# main.net
KiCad netlist of a schematic drawn in EAGLE
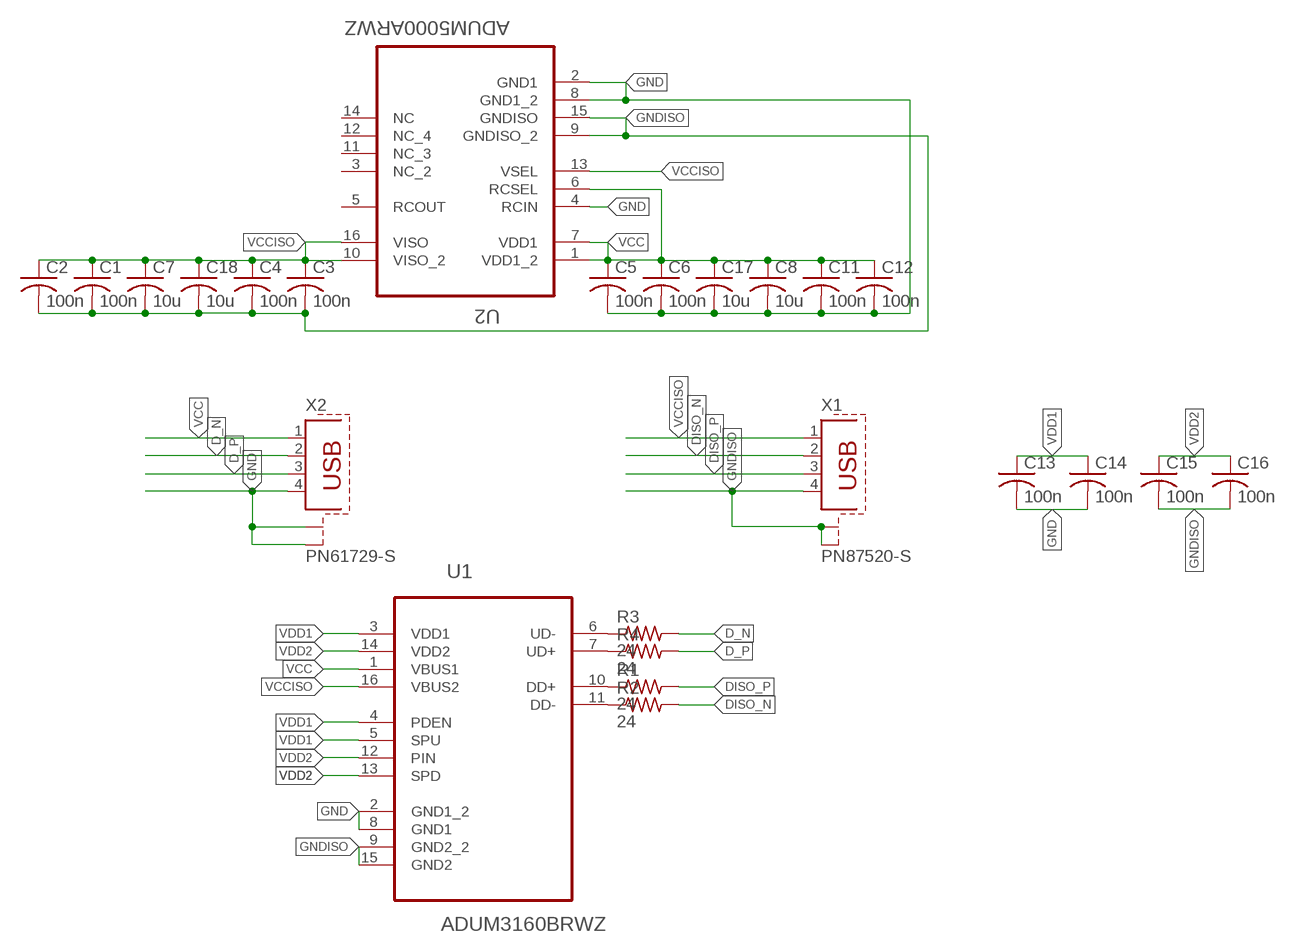
[diagram p0: schematic, sheet 1]

(export (version "E")
  (design (tool "Eeschema 10.0.6"))
  (components
    (comp (ref "C1")
      (value "100n")
      (footprint "eagle-import:C0603")
      (libsource (lib "eagle-import") (part "C-USC0603"))
    )
    (comp (ref "C2")
      (value "100n")
      (footprint "eagle-import:C0603")
      (libsource (lib "eagle-import") (part "C-USC0603"))
    )
    (comp (ref "C3")
      (value "100n")
      (footprint "eagle-import:C0603")
      (libsource (lib "eagle-import") (part "C-USC0603"))
    )
    (comp (ref "C4")
      (value "100n")
      (footprint "eagle-import:C0603")
      (libsource (lib "eagle-import") (part "C-USC0603"))
    )
    (comp (ref "C5")
      (value "100n")
      (footprint "eagle-import:C0603")
      (libsource (lib "eagle-import") (part "C-USC0603"))
    )
    (comp (ref "C6")
      (value "100n")
      (footprint "eagle-import:C0603")
      (libsource (lib "eagle-import") (part "C-USC0603"))
    )
    (comp (ref "C7")
      (value "10u")
      (footprint "eagle-import:C025-025X050")
      (libsource (lib "eagle-import") (part "C-US025-025X050"))
    )
    (comp (ref "C8")
      (value "10u")
      (footprint "eagle-import:C025-025X050")
      (libsource (lib "eagle-import") (part "C-US025-025X050"))
    )
    (comp (ref "C11")
      (value "100n")
      (footprint "eagle-import:C0603")
      (libsource (lib "eagle-import") (part "C-USC0603"))
    )
    (comp (ref "C12")
      (value "100n")
      (footprint "eagle-import:C0603")
      (libsource (lib "eagle-import") (part "C-USC0603"))
    )
    (comp (ref "C13")
      (value "100n")
      (footprint "eagle-import:C0603")
      (libsource (lib "eagle-import") (part "C-USC0603"))
    )
    (comp (ref "C14")
      (value "100n")
      (footprint "eagle-import:C0603")
      (libsource (lib "eagle-import") (part "C-USC0603"))
    )
    (comp (ref "C15")
      (value "100n")
      (footprint "eagle-import:C0603")
      (libsource (lib "eagle-import") (part "C-USC0603"))
    )
    (comp (ref "C16")
      (value "100n")
      (footprint "eagle-import:C0603")
      (libsource (lib "eagle-import") (part "C-USC0603"))
    )
    (comp (ref "C17")
      (value "10u")
      (footprint "eagle-import:C025-025X050")
      (libsource (lib "eagle-import") (part "C-US025-025X050"))
    )
    (comp (ref "C18")
      (value "10u")
      (footprint "eagle-import:C025-025X050")
      (libsource (lib "eagle-import") (part "C-US025-025X050"))
    )
    (comp (ref "R1")
      (value "24")
      (footprint "eagle-import:R0603")
      (libsource (lib "eagle-import") (part "R-US_R0603"))
    )
    (comp (ref "R2")
      (value "24")
      (footprint "eagle-import:R0603")
      (libsource (lib "eagle-import") (part "R-US_R0603"))
    )
    (comp (ref "R3")
      (value "24")
      (footprint "eagle-import:R0603")
      (libsource (lib "eagle-import") (part "R-US_R0603"))
    )
    (comp (ref "R4")
      (value "24")
      (footprint "eagle-import:R0603")
      (libsource (lib "eagle-import") (part "R-US_R0603"))
    )
    (comp (ref "U1")
      (value "ADUM3160BRWZ")
      (footprint "eagle-import:SOIC127P1032X265-16N")
      (libsource (lib "eagle-import") (part "ADUM3160BRWZ"))
    )
    (comp (ref "U2")
      (value "ADUM5000ARWZ")
      (footprint "eagle-import:SOIC127P1032X265-16N")
      (libsource (lib "eagle-import") (part "ADUM5000ARWZ"))
    )
    (comp (ref "X1")
      (value "PN87520-S")
      (footprint "eagle-import:PN87520-S")
      (libsource (lib "eagle-import") (part "PN87520-S"))
    )
    (comp (ref "X2")
      (value "PN61729-S")
      (footprint "eagle-import:PN61729-S")
      (libsource (lib "eagle-import") (part "PN61729-S"))
    )
  )
  (nets
    (net (code "1") (name "DISO_N") (class "Default")
      (node (ref "R2") (pin "2") (pinfunction "2_2") (pintype "passive"))
      (node (ref "X1") (pin "2") (pinfunction "2_2") (pintype "passive"))
    )
    (net (code "2") (name "DISO_P") (class "Default")
      (node (ref "R1") (pin "2") (pinfunction "2_2") (pintype "passive"))
      (node (ref "X1") (pin "3") (pinfunction "3_3") (pintype "passive"))
    )
    (net (code "3") (name "D_N") (class "Default")
      (node (ref "R3") (pin "2") (pinfunction "2_2") (pintype "passive"))
      (node (ref "X2") (pin "2") (pinfunction "2_2") (pintype "passive"))
    )
    (net (code "4") (name "D_P") (class "Default")
      (node (ref "R4") (pin "2") (pinfunction "2_2") (pintype "passive"))
      (node (ref "X2") (pin "3") (pinfunction "3_3") (pintype "passive"))
    )
    (net (code "5") (name "GND") (class "Default")
      (node (ref "C11") (pin "2") (pinfunction "2_2") (pintype "passive"))
      (node (ref "C12") (pin "2") (pinfunction "2_2") (pintype "passive"))
      (node (ref "C13") (pin "2") (pinfunction "2_2") (pintype "passive"))
      (node (ref "C14") (pin "2") (pinfunction "2_2") (pintype "passive"))
      (node (ref "C17") (pin "2") (pinfunction "2_2") (pintype "passive"))
      (node (ref "C5") (pin "2") (pinfunction "2_2") (pintype "passive"))
      (node (ref "C6") (pin "2") (pinfunction "2_2") (pintype "passive"))
      (node (ref "C8") (pin "2") (pinfunction "2_2") (pintype "passive"))
      (node (ref "U1") (pin "2") (pinfunction "GND1_2_2") (pintype "passive"))
      (node (ref "U1") (pin "8") (pinfunction "GND1_8") (pintype "passive"))
      (node (ref "U2") (pin "2") (pinfunction "GND1_2") (pintype "passive"))
      (node (ref "U2") (pin "4") (pinfunction "RCIN_4") (pintype "input"))
      (node (ref "U2") (pin "8") (pinfunction "GND1_2_8") (pintype "passive"))
      (node (ref "X2") (pin "4") (pinfunction "4_4") (pintype "passive"))
      (node (ref "X2") (pin "S1") (pinfunction "S1_S1") (pintype "passive"))
      (node (ref "X2") (pin "S2") (pinfunction "S2_S2") (pintype "passive"))
    )
    (net (code "6") (name "GNDISO") (class "Default")
      (node (ref "C1") (pin "2") (pinfunction "2_2") (pintype "passive"))
      (node (ref "C15") (pin "2") (pinfunction "2_2") (pintype "passive"))
      (node (ref "C16") (pin "2") (pinfunction "2_2") (pintype "passive"))
      (node (ref "C18") (pin "2") (pinfunction "2_2") (pintype "passive"))
      (node (ref "C2") (pin "2") (pinfunction "2_2") (pintype "passive"))
      (node (ref "C3") (pin "2") (pinfunction "2_2") (pintype "passive"))
      (node (ref "C4") (pin "2") (pinfunction "2_2") (pintype "passive"))
      (node (ref "C7") (pin "2") (pinfunction "2_2") (pintype "passive"))
      (node (ref "U1") (pin "15") (pinfunction "GND2_15") (pintype "passive"))
      (node (ref "U1") (pin "9") (pinfunction "GND2_2_9") (pintype "passive"))
      (node (ref "U2") (pin "15") (pinfunction "GNDISO_15") (pintype "passive"))
      (node (ref "U2") (pin "9") (pinfunction "GNDISO_2_9") (pintype "passive"))
      (node (ref "X1") (pin "4") (pinfunction "4_4") (pintype "passive"))
      (node (ref "X1") (pin "S1") (pinfunction "S1_S1") (pintype "passive"))
      (node (ref "X1") (pin "S2") (pinfunction "S2_S2") (pintype "passive"))
    )
    (net (code "7") (name "Net-(U1-DD+)") (class "Default")
      (node (ref "R1") (pin "1") (pinfunction "1_1") (pintype "passive"))
      (node (ref "U1") (pin "10") (pinfunction "DD+_10") (pintype "bidirectional"))
    )
    (net (code "8") (name "Net-(U1-DD-)") (class "Default")
      (node (ref "R2") (pin "1") (pinfunction "1_1") (pintype "passive"))
      (node (ref "U1") (pin "11") (pinfunction "DD-_11") (pintype "bidirectional"))
    )
    (net (code "9") (name "Net-(U1-UD+)") (class "Default")
      (node (ref "R4") (pin "1") (pinfunction "1_1") (pintype "passive"))
      (node (ref "U1") (pin "7") (pinfunction "UD+_7") (pintype "bidirectional"))
    )
    (net (code "10") (name "Net-(U1-UD-)") (class "Default")
      (node (ref "R3") (pin "1") (pinfunction "1_1") (pintype "passive"))
      (node (ref "U1") (pin "6") (pinfunction "UD-_6") (pintype "bidirectional"))
    )
    (net (code "11") (name "VCC") (class "Default")
      (node (ref "C11") (pin "1") (pinfunction "1_1") (pintype "passive"))
      (node (ref "C12") (pin "1") (pinfunction "1_1") (pintype "passive"))
      (node (ref "C17") (pin "1") (pinfunction "1_1") (pintype "passive"))
      (node (ref "C5") (pin "1") (pinfunction "1_1") (pintype "passive"))
      (node (ref "C6") (pin "1") (pinfunction "1_1") (pintype "passive"))
      (node (ref "C8") (pin "1") (pinfunction "1_1") (pintype "passive"))
      (node (ref "U1") (pin "1") (pinfunction "VBUS1_1") (pintype "power_in"))
      (node (ref "U2") (pin "1") (pinfunction "VDD1_2_1") (pintype "power_in"))
      (node (ref "U2") (pin "6") (pinfunction "RCSEL_6") (pintype "input"))
      (node (ref "U2") (pin "7") (pinfunction "VDD1_7") (pintype "power_in"))
      (node (ref "X2") (pin "1") (pinfunction "1_1") (pintype "passive"))
    )
    (net (code "12") (name "VCCISO") (class "Default")
      (node (ref "C1") (pin "1") (pinfunction "1_1") (pintype "passive"))
      (node (ref "C18") (pin "1") (pinfunction "1_1") (pintype "passive"))
      (node (ref "C2") (pin "1") (pinfunction "1_1") (pintype "passive"))
      (node (ref "C3") (pin "1") (pinfunction "1_1") (pintype "passive"))
      (node (ref "C4") (pin "1") (pinfunction "1_1") (pintype "passive"))
      (node (ref "C7") (pin "1") (pinfunction "1_1") (pintype "passive"))
      (node (ref "U1") (pin "16") (pinfunction "VBUS2_16") (pintype "power_in"))
      (node (ref "U2") (pin "10") (pinfunction "VISO_2_10") (pintype "output"))
      (node (ref "U2") (pin "13") (pinfunction "VSEL_13") (pintype "input"))
      (node (ref "U2") (pin "16") (pinfunction "VISO_16") (pintype "output"))
      (node (ref "X1") (pin "1") (pinfunction "1_1") (pintype "passive"))
    )
    (net (code "13") (name "VDD1") (class "Default")
      (node (ref "C13") (pin "1") (pinfunction "1_1") (pintype "passive"))
      (node (ref "C14") (pin "1") (pinfunction "1_1") (pintype "passive"))
      (node (ref "U1") (pin "3") (pinfunction "VDD1_3") (pintype "power_in"))
      (node (ref "U1") (pin "4") (pinfunction "PDEN_4") (pintype "input"))
      (node (ref "U1") (pin "5") (pinfunction "SPU_5") (pintype "input"))
    )
    (net (code "14") (name "VDD2") (class "Default")
      (node (ref "C15") (pin "1") (pinfunction "1_1") (pintype "passive"))
      (node (ref "C16") (pin "1") (pinfunction "1_1") (pintype "passive"))
      (node (ref "U1") (pin "12") (pinfunction "PIN_12") (pintype "input"))
      (node (ref "U1") (pin "13") (pinfunction "SPD_13") (pintype "input"))
      (node (ref "U1") (pin "14") (pinfunction "VDD2_14") (pintype "power_in"))
    )
    (net (code "15") (name "unconnected-(U2-NC-Pad14)") (class "Default")
      (node (ref "U2") (pin "14") (pinfunction "NC_14") (pintype "no_connect"))
    )
    (net (code "16") (name "unconnected-(U2-NC_2-Pad3)") (class "Default")
      (node (ref "U2") (pin "3") (pinfunction "NC_2_3") (pintype "no_connect"))
    )
    (net (code "17") (name "unconnected-(U2-NC_3-Pad11)") (class "Default")
      (node (ref "U2") (pin "11") (pinfunction "NC_3_11") (pintype "no_connect"))
    )
    (net (code "18") (name "unconnected-(U2-NC_4-Pad12)") (class "Default")
      (node (ref "U2") (pin "12") (pinfunction "NC_4_12") (pintype "no_connect"))
    )
    (net (code "19") (name "unconnected-(U2-RCOUT-Pad5)") (class "Default")
      (node (ref "U2") (pin "5") (pinfunction "RCOUT_5") (pintype "output"))
    )
  )
)
